# DCC_zDecoder.net
KiCad netlist of a schematic drawn in EAGLE
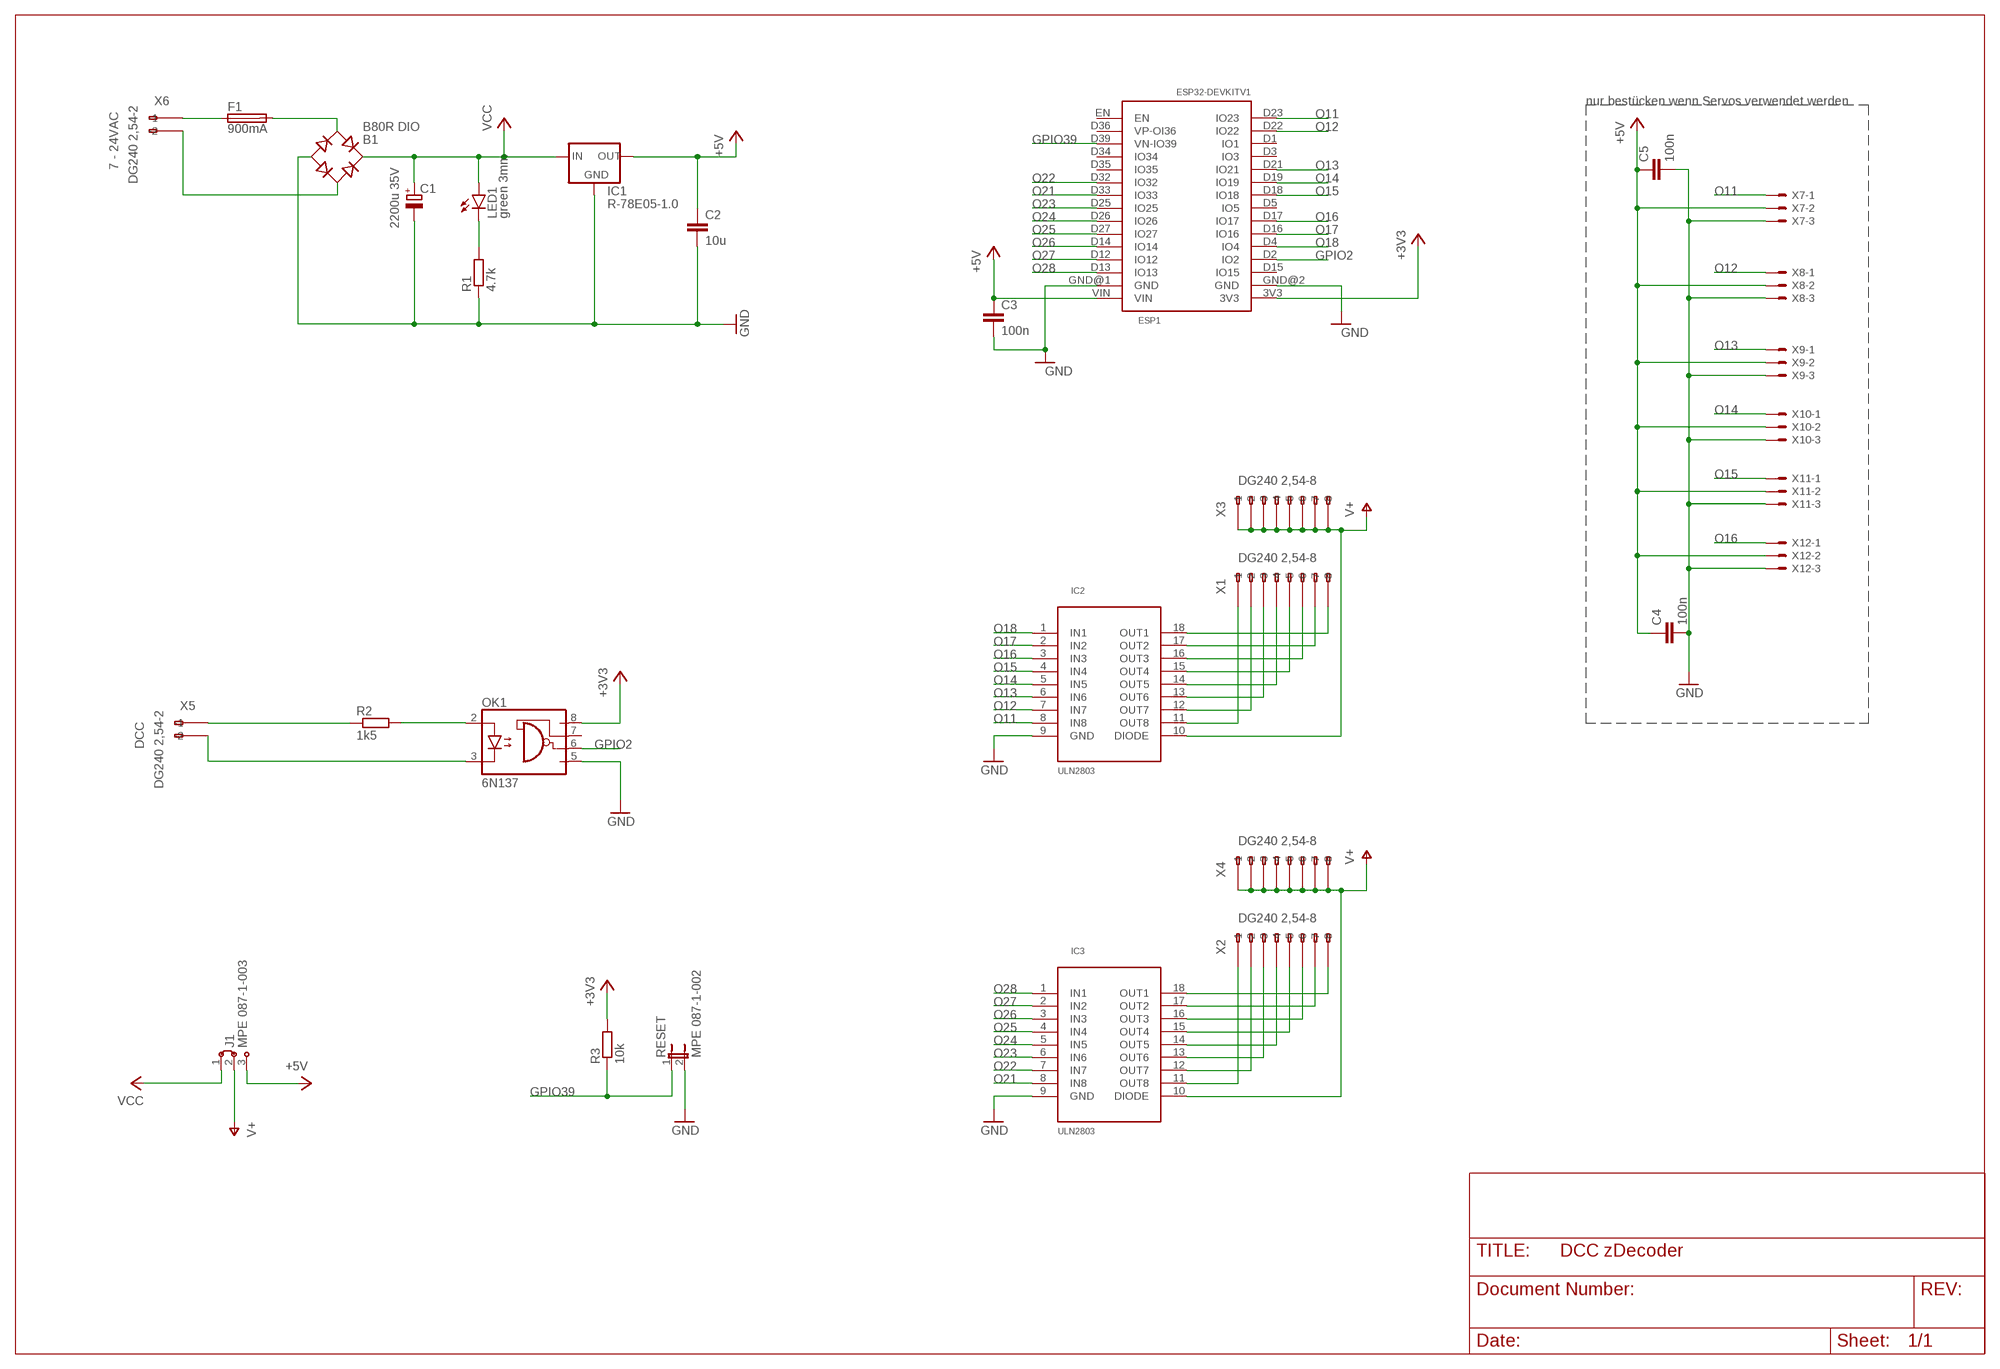
[diagram p0: schematic, sheet 1]

(export (version "E")
  (design (tool "Eeschema 10.0.6"))
  (components
    (comp (ref "B1")
      (value "B80R DIO")
      (footprint "eagle-import:RB1A")
      (libsource (lib "eagle-import") (part "RB1A"))
    )
    (comp (ref "C1")
      (value "2200u 35V")
      (footprint "eagle-import:E5-8,5")
      (libsource (lib "eagle-import") (part "CPOL-EUE5-8.5"))
    )
    (comp (ref "C2")
      (value "10u")
      (footprint "eagle-import:C050-024X044")
      (libsource (lib "eagle-import") (part "C-EU050-024X044"))
    )
    (comp (ref "C3")
      (value "100n")
      (footprint "eagle-import:C050-024X044")
      (libsource (lib "eagle-import") (part "C-EU050-024X044"))
    )
    (comp (ref "C4")
      (value "100n")
      (footprint "eagle-import:C050-024X044")
      (libsource (lib "eagle-import") (part "C-EU050-024X044"))
    )
    (comp (ref "C5")
      (value "100n")
      (footprint "eagle-import:C050-024X044")
      (libsource (lib "eagle-import") (part "C-EU050-024X044"))
    )
    (comp (ref "ESP1")
      (value "ESP32DEVKITV1")
      (footprint "eagle-import:ESP32-DEVKITV1")
      (libsource (lib "eagle-import") (part "ESP32DEVKITV1"))
    )
    (comp (ref "F1")
      (value "900mA")
      (footprint "eagle-import:TE5")
      (libsource (lib "eagle-import") (part "TE5"))
    )
    (comp (ref "IC1")
      (value "R-78E05-1.0")
      (footprint "eagle-import:R-78E-XX1.0")
      (libsource (lib "eagle-import") (part "R-78E-XX1.0"))
    )
    (comp (ref "IC2")
      (value "ULN2803")
      (footprint "eagle-import:DIL18")
      (libsource (lib "eagle-import") (part "ULN2803DIL18"))
    )
    (comp (ref "IC3")
      (value "ULN2803")
      (footprint "eagle-import:DIL18")
      (libsource (lib "eagle-import") (part "ULN2803DIL18"))
    )
    (comp (ref "J1")
      (value "MPE 087-1-003")
      (footprint "eagle-import:04C")
      (libsource (lib "eagle-import") (part "J2X2MM"))
    )
    (comp (ref "LED1")
      (value "green 3mm")
      (footprint "eagle-import:LED3MM")
      (fields (field (name "MF") "VISHAY SEMICONDUCTOR"))
      (libsource (lib "eagle-import") (part "TLLG4400"))
    )
    (comp (ref "OK1")
      (value "6N137")
      (footprint "eagle-import:DIL08")
      (libsource (lib "eagle-import") (part "6N137"))
    )
    (comp (ref "R1")
      (value "4.7k")
      (footprint "eagle-import:0207_10")
      (libsource (lib "eagle-import") (part "R-EU_0207/10"))
    )
    (comp (ref "R2")
      (value "1k5")
      (footprint "eagle-import:0207_10")
      (libsource (lib "eagle-import") (part "R-EU_0207/10"))
    )
    (comp (ref "R3")
      (value "10k")
      (footprint "eagle-import:0207_10")
      (libsource (lib "eagle-import") (part "R-EU_0207/10"))
    )
    (comp (ref "RESET")
      (value "MPE 087-1-002")
      (footprint "eagle-import:JP1")
      (libsource (lib "eagle-import") (part "JP1E"))
    )
    (comp (ref "X1")
      (value "DG240 2,54-8")
      (footprint "eagle-import:233-508")
      (fields (field (name "MF") "Wago Corporation") (field (name "MPN") "0233-0508"))
      (libsource (lib "eagle-import") (part "233-508"))
    )
    (comp (ref "X2")
      (value "DG240 2,54-8")
      (footprint "eagle-import:233-508")
      (fields (field (name "MF") "Wago Corporation") (field (name "MPN") "0233-0508"))
      (libsource (lib "eagle-import") (part "233-508"))
    )
    (comp (ref "X3")
      (value "DG240 2,54-8")
      (footprint "eagle-import:233-508")
      (fields (field (name "MF") "Wago Corporation") (field (name "MPN") "0233-0508"))
      (libsource (lib "eagle-import") (part "233-508"))
    )
    (comp (ref "X4")
      (value "DG240 2,54-8")
      (footprint "eagle-import:233-508")
      (fields (field (name "MF") "Wago Corporation") (field (name "MPN") "0233-0508"))
      (libsource (lib "eagle-import") (part "233-508"))
    )
    (comp (ref "X5")
      (value "DG240 2,54-2")
      (footprint "eagle-import:233-202")
      (fields (field (name "MPN") "233-202"))
      (libsource (lib "eagle-import") (part "233-202"))
    )
    (comp (ref "X6")
      (value "DG240 2,54-2")
      (footprint "eagle-import:233-202")
      (fields (field (name "MPN") "233-202"))
      (libsource (lib "eagle-import") (part "233-202"))
    )
    (comp (ref "X7")
      (value "PSS 254/3G")
      (footprint "eagle-import:22-23-2031")
      (fields (field (name "MF") "MOLEX") (field (name "MPN") "22-23-2031"))
      (libsource (lib "eagle-import") (part "22-23-2031"))
    )
    (comp (ref "X8")
      (value "PSS 254/3G")
      (footprint "eagle-import:22-23-2031")
      (fields (field (name "MF") "MOLEX") (field (name "MPN") "22-23-2031"))
      (libsource (lib "eagle-import") (part "22-23-2031"))
    )
    (comp (ref "X9")
      (value "PSS 254/3G")
      (footprint "eagle-import:22-23-2031")
      (fields (field (name "MF") "MOLEX") (field (name "MPN") "22-23-2031"))
      (libsource (lib "eagle-import") (part "22-23-2031"))
    )
    (comp (ref "X10")
      (value "PSS 254/3G")
      (footprint "eagle-import:22-23-2031")
      (fields (field (name "MF") "MOLEX") (field (name "MPN") "22-23-2031"))
      (libsource (lib "eagle-import") (part "22-23-2031"))
    )
    (comp (ref "X11")
      (value "PSS 254/3G")
      (footprint "eagle-import:22-23-2031")
      (fields (field (name "MF") "MOLEX") (field (name "MPN") "22-23-2031"))
      (libsource (lib "eagle-import") (part "22-23-2031"))
    )
    (comp (ref "X12")
      (value "PSS 254/3G")
      (footprint "eagle-import:22-23-2031")
      (fields (field (name "MF") "MOLEX") (field (name "MPN") "22-23-2031"))
      (libsource (lib "eagle-import") (part "22-23-2031"))
    )
  )
  (nets
    (net (code "1") (name "+3V3") (class "Default")
      (node (ref "ESP1") (pin "3V3") (pinfunction "3V3_3V3") (pintype "power_in"))
      (node (ref "OK1") (pin "8") (pinfunction "VCC_8") (pintype "passive"))
      (node (ref "R3") (pin "2") (pinfunction "2_2") (pintype "passive"))
    )
    (net (code "2") (name "+5V") (class "Default")
      (node (ref "C2") (pin "1") (pinfunction "1_1") (pintype "passive"))
      (node (ref "C3") (pin "1") (pinfunction "1_1") (pintype "passive"))
      (node (ref "C4") (pin "1") (pinfunction "1_1") (pintype "passive"))
      (node (ref "C5") (pin "1") (pinfunction "1_1") (pintype "passive"))
      (node (ref "ESP1") (pin "VIN") (pinfunction "VIN_VIN") (pintype "power_in"))
      (node (ref "IC1") (pin "OUT") (pinfunction "OUT_OUT") (pintype "passive"))
      (node (ref "J1") (pin "3") (pinfunction "3_3") (pintype "passive"))
      (node (ref "X10") (pin "2") (pinfunction "S_2") (pintype "passive"))
      (node (ref "X11") (pin "2") (pinfunction "S_2") (pintype "passive"))
      (node (ref "X12") (pin "2") (pinfunction "S_2") (pintype "passive"))
      (node (ref "X7") (pin "2") (pinfunction "S_2") (pintype "passive"))
      (node (ref "X8") (pin "2") (pinfunction "S_2") (pintype "passive"))
      (node (ref "X9") (pin "2") (pinfunction "S_2") (pintype "passive"))
    )
    (net (code "3") (name "/GPIO2") (class "Default")
      (node (ref "ESP1") (pin "D2") (pinfunction "IO2_D2") (pintype "bidirectional"))
      (node (ref "OK1") (pin "6") (pinfunction "VO_6") (pintype "passive"))
    )
    (net (code "4") (name "/GPIO39") (class "Default")
      (node (ref "ESP1") (pin "D39") (pinfunction "VN-IO39_D39") (pintype "bidirectional"))
      (node (ref "R3") (pin "1") (pinfunction "1_1") (pintype "passive"))
      (node (ref "RESET") (pin "1") (pinfunction "1_1") (pintype "passive"))
    )
    (net (code "5") (name "/O11") (class "Default")
      (node (ref "ESP1") (pin "D23") (pinfunction "IO23_D23") (pintype "bidirectional"))
      (node (ref "IC2") (pin "8") (pinfunction "IN8_8") (pintype "input"))
      (node (ref "X7") (pin "1") (pinfunction "S_1") (pintype "passive"))
    )
    (net (code "6") (name "/O12") (class "Default")
      (node (ref "ESP1") (pin "D22") (pinfunction "IO22_D22") (pintype "bidirectional"))
      (node (ref "IC2") (pin "7") (pinfunction "IN7_7") (pintype "input"))
      (node (ref "X8") (pin "1") (pinfunction "S_1") (pintype "passive"))
    )
    (net (code "7") (name "/O13") (class "Default")
      (node (ref "ESP1") (pin "D21") (pinfunction "IO21_D21") (pintype "bidirectional"))
      (node (ref "IC2") (pin "6") (pinfunction "IN6_6") (pintype "input"))
      (node (ref "X9") (pin "1") (pinfunction "S_1") (pintype "passive"))
    )
    (net (code "8") (name "/O14") (class "Default")
      (node (ref "ESP1") (pin "D19") (pinfunction "IO19_D19") (pintype "bidirectional"))
      (node (ref "IC2") (pin "5") (pinfunction "IN5_5") (pintype "input"))
      (node (ref "X10") (pin "1") (pinfunction "S_1") (pintype "passive"))
    )
    (net (code "9") (name "/O15") (class "Default")
      (node (ref "ESP1") (pin "D18") (pinfunction "IO18_D18") (pintype "bidirectional"))
      (node (ref "IC2") (pin "4") (pinfunction "IN4_4") (pintype "input"))
      (node (ref "X11") (pin "1") (pinfunction "S_1") (pintype "passive"))
    )
    (net (code "10") (name "/O16") (class "Default")
      (node (ref "ESP1") (pin "D17") (pinfunction "IO17_D17") (pintype "bidirectional"))
      (node (ref "IC2") (pin "3") (pinfunction "IN3_3") (pintype "input"))
      (node (ref "X12") (pin "1") (pinfunction "S_1") (pintype "passive"))
    )
    (net (code "11") (name "/O17") (class "Default")
      (node (ref "ESP1") (pin "D16") (pinfunction "IO16_D16") (pintype "bidirectional"))
      (node (ref "IC2") (pin "2") (pinfunction "IN2_2") (pintype "input"))
    )
    (net (code "12") (name "/O18") (class "Default")
      (node (ref "ESP1") (pin "D4") (pinfunction "IO4_D4") (pintype "bidirectional"))
      (node (ref "IC2") (pin "1") (pinfunction "IN1_1") (pintype "input"))
    )
    (net (code "13") (name "/O21") (class "Default")
      (node (ref "ESP1") (pin "D33") (pinfunction "IO33_D33") (pintype "bidirectional"))
      (node (ref "IC3") (pin "8") (pinfunction "IN8_8") (pintype "input"))
    )
    (net (code "14") (name "/O22") (class "Default")
      (node (ref "ESP1") (pin "D32") (pinfunction "IO32_D32") (pintype "bidirectional"))
      (node (ref "IC3") (pin "7") (pinfunction "IN7_7") (pintype "input"))
    )
    (net (code "15") (name "/O23") (class "Default")
      (node (ref "ESP1") (pin "D25") (pinfunction "IO25_D25") (pintype "bidirectional"))
      (node (ref "IC3") (pin "6") (pinfunction "IN6_6") (pintype "input"))
    )
    (net (code "16") (name "/O24") (class "Default")
      (node (ref "ESP1") (pin "D26") (pinfunction "IO26_D26") (pintype "bidirectional"))
      (node (ref "IC3") (pin "5") (pinfunction "IN5_5") (pintype "input"))
    )
    (net (code "17") (name "/O25") (class "Default")
      (node (ref "ESP1") (pin "D27") (pinfunction "IO27_D27") (pintype "bidirectional"))
      (node (ref "IC3") (pin "4") (pinfunction "IN4_4") (pintype "input"))
    )
    (net (code "18") (name "/O26") (class "Default")
      (node (ref "ESP1") (pin "D14") (pinfunction "IO14_D14") (pintype "bidirectional"))
      (node (ref "IC3") (pin "3") (pinfunction "IN3_3") (pintype "input"))
    )
    (net (code "19") (name "/O27") (class "Default")
      (node (ref "ESP1") (pin "D12") (pinfunction "IO12_D12") (pintype "bidirectional"))
      (node (ref "IC3") (pin "2") (pinfunction "IN2_2") (pintype "input"))
    )
    (net (code "20") (name "/O28") (class "Default")
      (node (ref "ESP1") (pin "D13") (pinfunction "IO13_D13") (pintype "bidirectional"))
      (node (ref "IC3") (pin "1") (pinfunction "IN1_1") (pintype "input"))
    )
    (net (code "21") (name "GND") (class "Default")
      (node (ref "B1") (pin "-") (pinfunction "-_-") (pintype "passive"))
      (node (ref "C1") (pin "-") (pinfunction "-_-") (pintype "passive"))
      (node (ref "C2") (pin "2") (pinfunction "2_2") (pintype "passive"))
      (node (ref "C3") (pin "2") (pinfunction "2_2") (pintype "passive"))
      (node (ref "C4") (pin "2") (pinfunction "2_2") (pintype "passive"))
      (node (ref "C5") (pin "2") (pinfunction "2_2") (pintype "passive"))
      (node (ref "ESP1") (pin "GND@1") (pinfunction "GND_GND@1") (pintype "power_in"))
      (node (ref "ESP1") (pin "GND@2") (pinfunction "GND_GND@2") (pintype "power_in"))
      (node (ref "IC1") (pin "GND") (pinfunction "GND_GND") (pintype "input"))
      (node (ref "IC2") (pin "9") (pinfunction "GND_9") (pintype "power_in"))
      (node (ref "IC3") (pin "9") (pinfunction "GND_9") (pintype "power_in"))
      (node (ref "OK1") (pin "5") (pinfunction "GND_5") (pintype "passive"))
      (node (ref "R1") (pin "1") (pinfunction "1_1") (pintype "passive"))
      (node (ref "RESET") (pin "2") (pinfunction "2_2") (pintype "passive"))
      (node (ref "X10") (pin "3") (pinfunction "S_3") (pintype "passive"))
      (node (ref "X11") (pin "3") (pinfunction "S_3") (pintype "passive"))
      (node (ref "X12") (pin "3") (pinfunction "S_3") (pintype "passive"))
      (node (ref "X7") (pin "3") (pinfunction "S_3") (pintype "passive"))
      (node (ref "X8") (pin "3") (pinfunction "S_3") (pintype "passive"))
      (node (ref "X9") (pin "3") (pinfunction "S_3") (pintype "passive"))
    )
    (net (code "22") (name "Net-(B1-PadAC1)") (class "Default")
      (node (ref "B1") (pin "AC1") (pinfunction "AC1_AC1") (pintype "passive"))
      (node (ref "F1") (pin "2") (pinfunction "2_2") (pintype "passive"))
    )
    (net (code "23") (name "Net-(IC2-OUT1)") (class "Default")
      (node (ref "IC2") (pin "18") (pinfunction "OUT1_18") (pintype "open_collector"))
      (node (ref "X1") (pin "A8") (pinfunction "-8_A8") (pintype "passive"))
    )
    (net (code "24") (name "Net-(IC2-OUT2)") (class "Default")
      (node (ref "IC2") (pin "17") (pinfunction "OUT2_17") (pintype "open_collector"))
      (node (ref "X1") (pin "A7") (pinfunction "-7_A7") (pintype "passive"))
    )
    (net (code "25") (name "Net-(IC2-OUT3)") (class "Default")
      (node (ref "IC2") (pin "16") (pinfunction "OUT3_16") (pintype "open_collector"))
      (node (ref "X1") (pin "A6") (pinfunction "-6_A6") (pintype "passive"))
    )
    (net (code "26") (name "Net-(IC2-OUT4)") (class "Default")
      (node (ref "IC2") (pin "15") (pinfunction "OUT4_15") (pintype "open_collector"))
      (node (ref "X1") (pin "A5") (pinfunction "-5_A5") (pintype "passive"))
    )
    (net (code "27") (name "Net-(IC2-OUT5)") (class "Default")
      (node (ref "IC2") (pin "14") (pinfunction "OUT5_14") (pintype "open_collector"))
      (node (ref "X1") (pin "A4") (pinfunction "-4_A4") (pintype "passive"))
    )
    (net (code "28") (name "Net-(IC2-OUT6)") (class "Default")
      (node (ref "IC2") (pin "13") (pinfunction "OUT6_13") (pintype "open_collector"))
      (node (ref "X1") (pin "A3") (pinfunction "-3_A3") (pintype "passive"))
    )
    (net (code "29") (name "Net-(IC2-OUT7)") (class "Default")
      (node (ref "IC2") (pin "12") (pinfunction "OUT7_12") (pintype "open_collector"))
      (node (ref "X1") (pin "A2") (pinfunction "-2_A2") (pintype "passive"))
    )
    (net (code "30") (name "Net-(IC2-OUT8)") (class "Default")
      (node (ref "IC2") (pin "11") (pinfunction "OUT8_11") (pintype "open_collector"))
      (node (ref "X1") (pin "A1") (pinfunction "-1_A1") (pintype "passive"))
    )
    (net (code "31") (name "Net-(IC3-OUT1)") (class "Default")
      (node (ref "IC3") (pin "18") (pinfunction "OUT1_18") (pintype "open_collector"))
      (node (ref "X2") (pin "A8") (pinfunction "-8_A8") (pintype "passive"))
    )
    (net (code "32") (name "Net-(IC3-OUT2)") (class "Default")
      (node (ref "IC3") (pin "17") (pinfunction "OUT2_17") (pintype "open_collector"))
      (node (ref "X2") (pin "A7") (pinfunction "-7_A7") (pintype "passive"))
    )
    (net (code "33") (name "Net-(IC3-OUT3)") (class "Default")
      (node (ref "IC3") (pin "16") (pinfunction "OUT3_16") (pintype "open_collector"))
      (node (ref "X2") (pin "A6") (pinfunction "-6_A6") (pintype "passive"))
    )
    (net (code "34") (name "Net-(IC3-OUT4)") (class "Default")
      (node (ref "IC3") (pin "15") (pinfunction "OUT4_15") (pintype "open_collector"))
      (node (ref "X2") (pin "A5") (pinfunction "-5_A5") (pintype "passive"))
    )
    (net (code "35") (name "Net-(IC3-OUT5)") (class "Default")
      (node (ref "IC3") (pin "14") (pinfunction "OUT5_14") (pintype "open_collector"))
      (node (ref "X2") (pin "A4") (pinfunction "-4_A4") (pintype "passive"))
    )
    (net (code "36") (name "Net-(IC3-OUT6)") (class "Default")
      (node (ref "IC3") (pin "13") (pinfunction "OUT6_13") (pintype "open_collector"))
      (node (ref "X2") (pin "A3") (pinfunction "-3_A3") (pintype "passive"))
    )
    (net (code "37") (name "Net-(IC3-OUT7)") (class "Default")
      (node (ref "IC3") (pin "12") (pinfunction "OUT7_12") (pintype "open_collector"))
      (node (ref "X2") (pin "A2") (pinfunction "-2_A2") (pintype "passive"))
    )
    (net (code "38") (name "Net-(IC3-OUT8)") (class "Default")
      (node (ref "IC3") (pin "11") (pinfunction "OUT8_11") (pintype "open_collector"))
      (node (ref "X2") (pin "A1") (pinfunction "-1_A1") (pintype "passive"))
    )
    (net (code "39") (name "Net-(LED1-C)") (class "Default")
      (node (ref "LED1") (pin "K") (pinfunction "C_K") (pintype "passive"))
      (node (ref "R1") (pin "2") (pinfunction "2_2") (pintype "passive"))
    )
    (net (code "40") (name "Net-(OK1-A)") (class "Default")
      (node (ref "OK1") (pin "2") (pinfunction "A_2") (pintype "passive"))
      (node (ref "R2") (pin "2") (pinfunction "2_2") (pintype "passive"))
    )
    (net (code "41") (name "Net-(OK1-C)") (class "Default")
      (node (ref "OK1") (pin "3") (pinfunction "C_3") (pintype "passive"))
      (node (ref "X5") (pin "A2") (pinfunction "-2_A2") (pintype "passive"))
    )
    (net (code "42") (name "Net-(X5--1)") (class "Default")
      (node (ref "R2") (pin "1") (pinfunction "1_1") (pintype "passive"))
      (node (ref "X5") (pin "A1") (pinfunction "-1_A1") (pintype "passive"))
    )
    (net (code "43") (name "Net-(X6--1)") (class "Default")
      (node (ref "F1") (pin "1") (pinfunction "1_1") (pintype "passive"))
      (node (ref "X6") (pin "A1") (pinfunction "-1_A1") (pintype "passive"))
    )
    (net (code "44") (name "Net-(X6--2)") (class "Default")
      (node (ref "B1") (pin "AC2") (pinfunction "AC2_AC2") (pintype "passive"))
      (node (ref "X6") (pin "A2") (pinfunction "-2_A2") (pintype "passive"))
    )
    (net (code "45") (name "V+") (class "Default")
      (node (ref "IC2") (pin "10") (pinfunction "DIODE_10") (pintype "power_in"))
      (node (ref "IC3") (pin "10") (pinfunction "DIODE_10") (pintype "power_in"))
      (node (ref "J1") (pin "2") (pinfunction "2_2") (pintype "passive"))
      (node (ref "X3") (pin "A1") (pinfunction "-1_A1") (pintype "passive"))
      (node (ref "X3") (pin "A2") (pinfunction "-2_A2") (pintype "passive"))
      (node (ref "X3") (pin "A3") (pinfunction "-3_A3") (pintype "passive"))
      (node (ref "X3") (pin "A4") (pinfunction "-4_A4") (pintype "passive"))
      (node (ref "X3") (pin "A5") (pinfunction "-5_A5") (pintype "passive"))
      (node (ref "X3") (pin "A6") (pinfunction "-6_A6") (pintype "passive"))
      (node (ref "X3") (pin "A7") (pinfunction "-7_A7") (pintype "passive"))
      (node (ref "X3") (pin "A8") (pinfunction "-8_A8") (pintype "passive"))
      (node (ref "X4") (pin "A1") (pinfunction "-1_A1") (pintype "passive"))
      (node (ref "X4") (pin "A2") (pinfunction "-2_A2") (pintype "passive"))
      (node (ref "X4") (pin "A3") (pinfunction "-3_A3") (pintype "passive"))
      (node (ref "X4") (pin "A4") (pinfunction "-4_A4") (pintype "passive"))
      (node (ref "X4") (pin "A5") (pinfunction "-5_A5") (pintype "passive"))
      (node (ref "X4") (pin "A6") (pinfunction "-6_A6") (pintype "passive"))
      (node (ref "X4") (pin "A7") (pinfunction "-7_A7") (pintype "passive"))
      (node (ref "X4") (pin "A8") (pinfunction "-8_A8") (pintype "passive"))
    )
    (net (code "46") (name "VCC") (class "Default")
      (node (ref "B1") (pin "+") (pinfunction "+_+") (pintype "passive"))
      (node (ref "C1") (pin "+") (pinfunction "+_+") (pintype "passive"))
      (node (ref "IC1") (pin "IN") (pinfunction "IN_IN") (pintype "input"))
      (node (ref "J1") (pin "1") (pinfunction "1_1") (pintype "passive"))
      (node (ref "LED1") (pin "A") (pinfunction "A_A") (pintype "passive"))
    )
    (net (code "47") (name "unconnected-(ESP1-IO1-PadD1)") (class "Default")
      (node (ref "ESP1") (pin "D1") (pinfunction "IO1_D1") (pintype "bidirectional"))
    )
    (net (code "48") (name "unconnected-(ESP1-IO3-PadD3)") (class "Default")
      (node (ref "ESP1") (pin "D3") (pinfunction "IO3_D3") (pintype "bidirectional"))
    )
    (net (code "49") (name "unconnected-(ESP1-IO5-PadD5)") (class "Default")
      (node (ref "ESP1") (pin "D5") (pinfunction "IO5_D5") (pintype "bidirectional"))
    )
    (net (code "50") (name "unconnected-(ESP1-IO15-PadD15)") (class "Default")
      (node (ref "ESP1") (pin "D15") (pinfunction "IO15_D15") (pintype "bidirectional"))
    )
    (net (code "51") (name "unconnected-(ESP1-IO34-PadD34)") (class "Default")
      (node (ref "ESP1") (pin "D34") (pinfunction "IO34_D34") (pintype "bidirectional"))
    )
    (net (code "52") (name "unconnected-(ESP1-IO35-PadD35)") (class "Default")
      (node (ref "ESP1") (pin "D35") (pinfunction "IO35_D35") (pintype "bidirectional"))
    )
    (net (code "53") (name "unconnected-(ESP1-PadEN)") (class "Default")
      (node (ref "ESP1") (pin "EN") (pinfunction "EN_EN") (pintype "bidirectional"))
    )
    (net (code "54") (name "unconnected-(ESP1-VP-OI36-PadD36)") (class "Default")
      (node (ref "ESP1") (pin "D36") (pinfunction "VP-OI36_D36") (pintype "bidirectional"))
    )
    (net (code "55") (name "unconnected-(OK1-VE-Pad7)") (class "Default")
      (node (ref "OK1") (pin "7") (pinfunction "VE_7") (pintype "passive"))
    )
    (net (code "56") (name "unconnected-(X1-B-1-PadB1)") (class "Default")
      (node (ref "X1") (pin "B1") (pinfunction "B-1_B1") (pintype "passive"))
    )
    (net (code "57") (name "unconnected-(X1-B-2-PadB2)") (class "Default")
      (node (ref "X1") (pin "B2") (pinfunction "B-2_B2") (pintype "passive"))
    )
    (net (code "58") (name "unconnected-(X1-B-3-PadB3)") (class "Default")
      (node (ref "X1") (pin "B3") (pinfunction "B-3_B3") (pintype "passive"))
    )
    (net (code "59") (name "unconnected-(X1-B-4-PadB4)") (class "Default")
      (node (ref "X1") (pin "B4") (pinfunction "B-4_B4") (pintype "passive"))
    )
    (net (code "60") (name "unconnected-(X1-B-5-PadB5)") (class "Default")
      (node (ref "X1") (pin "B5") (pinfunction "B-5_B5") (pintype "passive"))
    )
    (net (code "61") (name "unconnected-(X1-B-6-PadB6)") (class "Default")
      (node (ref "X1") (pin "B6") (pinfunction "B-6_B6") (pintype "passive"))
    )
    (net (code "62") (name "unconnected-(X1-B-7-PadB7)") (class "Default")
      (node (ref "X1") (pin "B7") (pinfunction "B-7_B7") (pintype "passive"))
    )
    (net (code "63") (name "unconnected-(X1-B-8-PadB8)") (class "Default")
      (node (ref "X1") (pin "B8") (pinfunction "B-8_B8") (pintype "passive"))
    )
    (net (code "64") (name "unconnected-(X2-B-1-PadB1)") (class "Default")
      (node (ref "X2") (pin "B1") (pinfunction "B-1_B1") (pintype "passive"))
    )
    (net (code "65") (name "unconnected-(X2-B-2-PadB2)") (class "Default")
      (node (ref "X2") (pin "B2") (pinfunction "B-2_B2") (pintype "passive"))
    )
    (net (code "66") (name "unconnected-(X2-B-3-PadB3)") (class "Default")
      (node (ref "X2") (pin "B3") (pinfunction "B-3_B3") (pintype "passive"))
    )
    (net (code "67") (name "unconnected-(X2-B-4-PadB4)") (class "Default")
      (node (ref "X2") (pin "B4") (pinfunction "B-4_B4") (pintype "passive"))
    )
    (net (code "68") (name "unconnected-(X2-B-5-PadB5)") (class "Default")
      (node (ref "X2") (pin "B5") (pinfunction "B-5_B5") (pintype "passive"))
    )
    (net (code "69") (name "unconnected-(X2-B-6-PadB6)") (class "Default")
      (node (ref "X2") (pin "B6") (pinfunction "B-6_B6") (pintype "passive"))
    )
    (net (code "70") (name "unconnected-(X2-B-7-PadB7)") (class "Default")
      (node (ref "X2") (pin "B7") (pinfunction "B-7_B7") (pintype "passive"))
    )
    (net (code "71") (name "unconnected-(X2-B-8-PadB8)") (class "Default")
      (node (ref "X2") (pin "B8") (pinfunction "B-8_B8") (pintype "passive"))
    )
    (net (code "72") (name "unconnected-(X3-B-1-PadB1)") (class "Default")
      (node (ref "X3") (pin "B1") (pinfunction "B-1_B1") (pintype "passive"))
    )
    (net (code "73") (name "unconnected-(X3-B-2-PadB2)") (class "Default")
      (node (ref "X3") (pin "B2") (pinfunction "B-2_B2") (pintype "passive"))
    )
    (net (code "74") (name "unconnected-(X3-B-3-PadB3)") (class "Default")
      (node (ref "X3") (pin "B3") (pinfunction "B-3_B3") (pintype "passive"))
    )
    (net (code "75") (name "unconnected-(X3-B-4-PadB4)") (class "Default")
      (node (ref "X3") (pin "B4") (pinfunction "B-4_B4") (pintype "passive"))
    )
    (net (code "76") (name "unconnected-(X3-B-5-PadB5)") (class "Default")
      (node (ref "X3") (pin "B5") (pinfunction "B-5_B5") (pintype "passive"))
    )
    (net (code "77") (name "unconnected-(X3-B-6-PadB6)") (class "Default")
      (node (ref "X3") (pin "B6") (pinfunction "B-6_B6") (pintype "passive"))
    )
    (net (code "78") (name "unconnected-(X3-B-7-PadB7)") (class "Default")
      (node (ref "X3") (pin "B7") (pinfunction "B-7_B7") (pintype "passive"))
    )
    (net (code "79") (name "unconnected-(X3-B-8-PadB8)") (class "Default")
      (node (ref "X3") (pin "B8") (pinfunction "B-8_B8") (pintype "passive"))
    )
    (net (code "80") (name "unconnected-(X4-B-1-PadB1)") (class "Default")
      (node (ref "X4") (pin "B1") (pinfunction "B-1_B1") (pintype "passive"))
    )
    (net (code "81") (name "unconnected-(X4-B-2-PadB2)") (class "Default")
      (node (ref "X4") (pin "B2") (pinfunction "B-2_B2") (pintype "passive"))
    )
    (net (code "82") (name "unconnected-(X4-B-3-PadB3)") (class "Default")
      (node (ref "X4") (pin "B3") (pinfunction "B-3_B3") (pintype "passive"))
    )
    (net (code "83") (name "unconnected-(X4-B-4-PadB4)") (class "Default")
      (node (ref "X4") (pin "B4") (pinfunction "B-4_B4") (pintype "passive"))
    )
    (net (code "84") (name "unconnected-(X4-B-5-PadB5)") (class "Default")
      (node (ref "X4") (pin "B5") (pinfunction "B-5_B5") (pintype "passive"))
    )
    (net (code "85") (name "unconnected-(X4-B-6-PadB6)") (class "Default")
      (node (ref "X4") (pin "B6") (pinfunction "B-6_B6") (pintype "passive"))
    )
    (net (code "86") (name "unconnected-(X4-B-7-PadB7)") (class "Default")
      (node (ref "X4") (pin "B7") (pinfunction "B-7_B7") (pintype "passive"))
    )
    (net (code "87") (name "unconnected-(X4-B-8-PadB8)") (class "Default")
      (node (ref "X4") (pin "B8") (pinfunction "B-8_B8") (pintype "passive"))
    )
    (net (code "88") (name "unconnected-(X5-B-1-PadB1)") (class "Default")
      (node (ref "X5") (pin "B1") (pinfunction "B-1_B1") (pintype "passive"))
    )
    (net (code "89") (name "unconnected-(X5-B-2-PadB2)") (class "Default")
      (node (ref "X5") (pin "B2") (pinfunction "B-2_B2") (pintype "passive"))
    )
    (net (code "90") (name "unconnected-(X6-B-1-PadB1)") (class "Default")
      (node (ref "X6") (pin "B1") (pinfunction "B-1_B1") (pintype "passive"))
    )
    (net (code "91") (name "unconnected-(X6-B-2-PadB2)") (class "Default")
      (node (ref "X6") (pin "B2") (pinfunction "B-2_B2") (pintype "passive"))
    )
  )
)
